# CAN_Sheet.net
KiCad netlist of a schematic drawn in Altium Designer
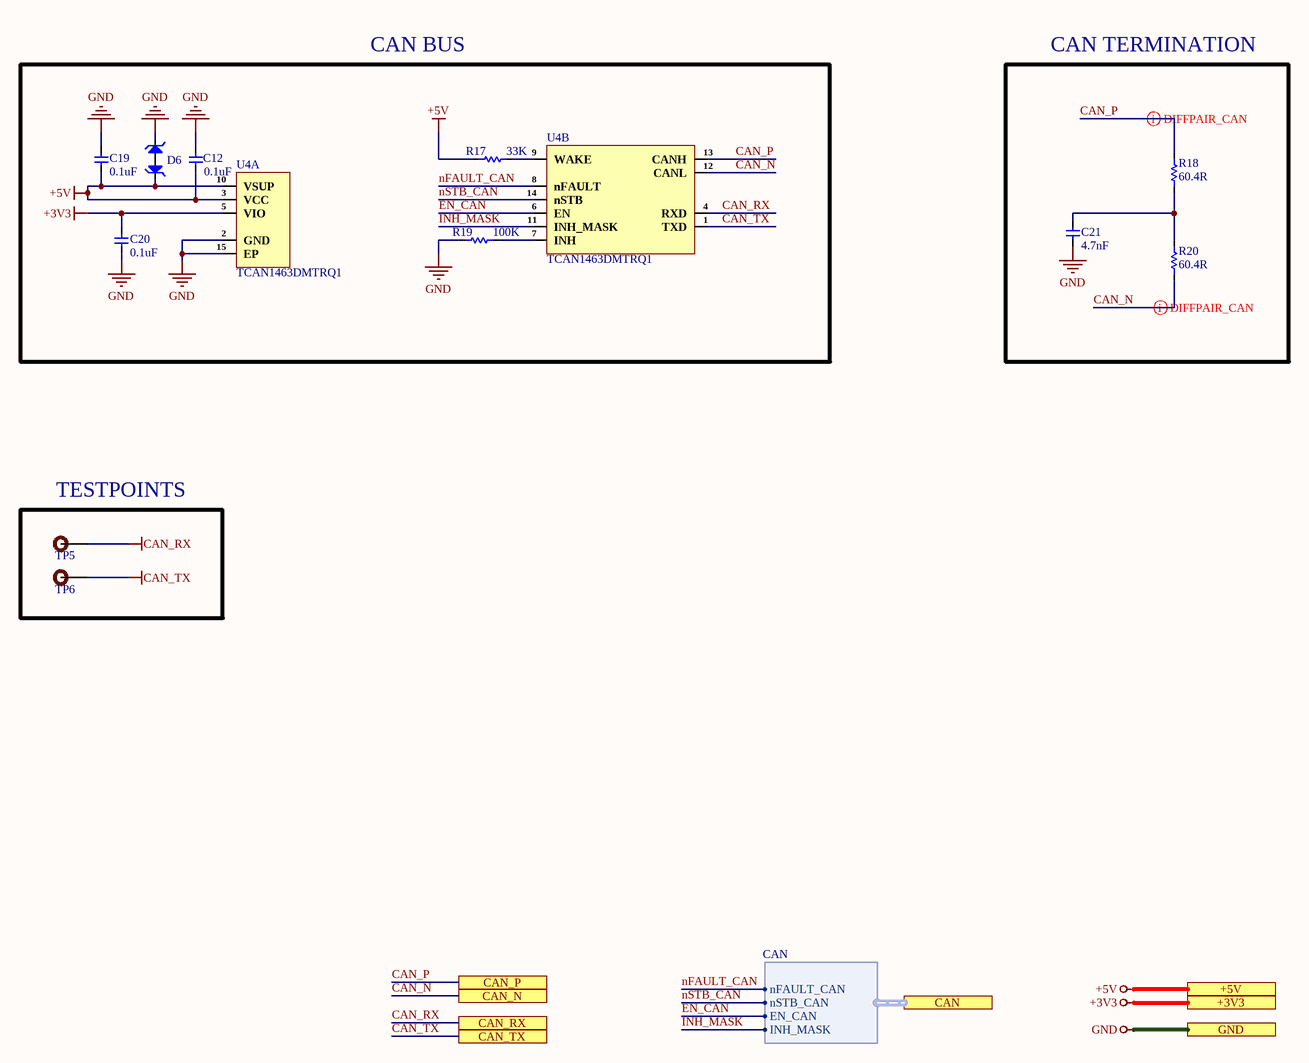
[diagram p0: CAN_Sheet.SchDoc]

(export (version "E")
  (design (tool "Eeschema 10.0.6"))
  (components
    (comp (ref "C12")
      (value "0.1uF")
      (footprint "Cap-0402")
      (description "CAP CER 0.1UF 16V X7R 0402")
      (fields
        (field (name "MANUFACTURER") "Yageo")
        (field (name "MANUFACTURER PART NUMBER") "CC0402JRX7R7BB104")
      )
      (libsource (lib "eSpark Libraries") (part "CC0402JRX7R7BB104"))
    )
    (comp (ref "C19")
      (value "0.1uF")
      (footprint "Cap-0402")
      (description "CAP CER 0.1UF 16V X7R 0402")
      (fields
        (field (name "MANUFACTURER") "Yageo")
        (field (name "MANUFACTURER PART NUMBER") "CC0402JRX7R7BB104")
      )
      (libsource (lib "eSpark Libraries") (part "CC0402JRX7R7BB104"))
    )
    (comp (ref "C20")
      (value "0.1uF")
      (footprint "Cap-0402")
      (description "CAP CER 0.1UF 16V X7R 0402")
      (fields
        (field (name "MANUFACTURER") "Yageo")
        (field (name "MANUFACTURER PART NUMBER") "CC0402JRX7R7BB104")
      )
      (libsource (lib "eSpark Libraries") (part "CC0402JRX7R7BB104"))
    )
    (comp (ref "C21")
      (value "4.7nF")
      (footprint "Cap-0402")
      (description "CAP CER 4700PF 50V X7R 0402")
      (fields
        (field (name "MANUFACTURER") "Yageo")
        (field (name "MANUFACTURER PART NUMBER") "CC0402KRX7R9BB472")
      )
      (libsource (lib "eSpark Libraries") (part "CC0402KRX7R9BB472"))
    )
    (comp (ref "D6")
      (value "PESD5V0H1BSFYL")
      (footprint "DSN0603-2")
      (description "TVS DIODE 5VWM 6.3VC DSN0603-2")
      (fields (field (name "MANUFACTURER") "Nexperia") (field (name "LCSC PART NUMBER") "C477989"))
      (libsource (lib "eSpark Libraries") (part "PESD5V0H1BSFYL"))
    )
    (comp (ref "R17")
      (value "33K")
      (footprint "Res-0402")
      (description "RES 33K OHM 1% 1/16W 0402")
      (fields
        (field (name "MANUFACTURER") "YAGEO")
        (field (name "MANUFACTURER PART NUMBER") "RC0402FR-0733KL")
      )
      (libsource (lib "eSpark Libraries") (part "RC0402FR-0733KL"))
    )
    (comp (ref "R18")
      (value "60.4R")
      (footprint "Res-0603")
      (description "100mW Thick Film Resistors ±100ppm/℃ ±1% 60.4Ω 0603 Chip Resistor - Surface Mount ROHS")
      (fields
        (field (name "MANUFACTURER PART NUMBER") "RTT0360R4FTP")
        (field (name "LCSC PART NUMBER") "C103744")
      )
      (libsource (lib "eSpark Libraries") (part "RTT0360R4FTP"))
    )
    (comp (ref "R19")
      (value "100K")
      (footprint "Res-0402")
      (description "RES 100K OHM 1% 1/16W 0402")
      (fields
        (field (name "MANUFACTURER") "Yageo")
        (field (name "MANUFACTURER PART NUMBER") "RC0402FR-07100KL")
      )
      (libsource (lib "eSpark Libraries") (part "RC0402FR-07100KL"))
    )
    (comp (ref "R20")
      (value "60.4R")
      (footprint "Res-0603")
      (description "100mW Thick Film Resistors ±100ppm/℃ ±1% 60.4Ω 0603 Chip Resistor - Surface Mount ROHS")
      (fields
        (field (name "MANUFACTURER PART NUMBER") "RTT0360R4FTP")
        (field (name "LCSC PART NUMBER") "C103744")
      )
      (libsource (lib "eSpark Libraries") (part "RTT0360R4FTP"))
    )
    (comp (ref "TP5")
      (value "TEST POINT")
      (footprint "Test-point")
      (description "Test Point ON")
      (libsource (lib "eSpark Libraries") (part "TEST POINT"))
    )
    (comp (ref "TP6")
      (value "TEST POINT")
      (footprint "Test-point")
      (description "Test Point ON")
      (libsource (lib "eSpark Libraries") (part "TEST POINT"))
    )
    (comp (ref "U4")
      (value "TCAN1463DMTRQ1")
      (footprint "VSON-14(3x4.5)")
      (description "IC TRANSCEIVER HALF 1/1 14VSON")
      (fields (field (name "MANUFACTURER") "Texas Instruments") (field (name "LCSC PART NUMBER") "C5215823"))
      (libsource (lib "eSpark Libraries") (part "TCAN1463DMTRQ1"))
    )
  )
  (nets
    (net (code "2") (name "+3V3") (class "Default")
      (node (ref "C20") (pin "2") (pinfunction "2_2") (pintype "passive"))
      (node (ref "U4") (pin "5") (pinfunction "VIO_5") (pintype "passive"))
    )
    (net (code "3") (name "+5V") (class "Default")
      (node (ref "C12") (pin "1") (pinfunction "1_1") (pintype "passive"))
      (node (ref "C19") (pin "1") (pinfunction "1_1") (pintype "passive"))
      (node (ref "D6") (pin "1") (pinfunction "1_1") (pintype "passive"))
      (node (ref "R17") (pin "1") (pinfunction "1_1") (pintype "passive"))
      (node (ref "U4") (pin "10") (pinfunction "VSUP_10") (pintype "passive"))
      (node (ref "U4") (pin "3") (pinfunction "VCC_3") (pintype "passive"))
    )
    (net (code "4") (name "/CAN_N") (class "Default")
      (node (ref "R20") (pin "2") (pinfunction "2_2") (pintype "passive"))
      (node (ref "U4") (pin "12") (pinfunction "CANL_12") (pintype "passive"))
    )
    (net (code "5") (name "/CAN_P") (class "Default")
      (node (ref "R18") (pin "1") (pinfunction "1_1") (pintype "passive"))
      (node (ref "U4") (pin "13") (pinfunction "CANH_13") (pintype "passive"))
    )
    (net (code "6") (name "/EN_CAN") (class "Default")
      (node (ref "U4") (pin "6") (pinfunction "EN_6") (pintype "passive"))
    )
    (net (code "7") (name "/INH_MASK") (class "Default")
      (node (ref "U4") (pin "11") (pinfunction "INH_MASK_11") (pintype "passive"))
    )
    (net (code "8") (name "/nFAULT_CAN") (class "Default")
      (node (ref "U4") (pin "8") (pinfunction "nFAULT_8") (pintype "passive"))
    )
    (net (code "9") (name "/nSTB_CAN") (class "Default")
      (node (ref "U4") (pin "14") (pinfunction "nSTB_14") (pintype "passive"))
    )
    (net (code "11") (name "CAN_RX") (class "Default")
      (node (ref "TP5") (pin "1") (pinfunction "1_1") (pintype "passive"))
      (node (ref "U4") (pin "4") (pinfunction "RXD_4") (pintype "passive"))
    )
    (net (code "12") (name "CAN_TX") (class "Default")
      (node (ref "TP6") (pin "1") (pinfunction "1_1") (pintype "passive"))
      (node (ref "U4") (pin "1") (pinfunction "TXD_1") (pintype "passive"))
    )
    (net (code "13") (name "GND") (class "Default")
      (node (ref "C12") (pin "2") (pinfunction "2_2") (pintype "passive"))
      (node (ref "C19") (pin "2") (pinfunction "2_2") (pintype "passive"))
      (node (ref "C20") (pin "1") (pinfunction "1_1") (pintype "passive"))
      (node (ref "C21") (pin "2") (pinfunction "2_2") (pintype "passive"))
      (node (ref "D6") (pin "2") (pinfunction "2_2") (pintype "passive"))
      (node (ref "R19") (pin "1") (pinfunction "1_1") (pintype "passive"))
      (node (ref "U4") (pin "15") (pinfunction "EP_15") (pintype "passive"))
      (node (ref "U4") (pin "2") (pinfunction "GND_2") (pintype "passive"))
    )
    (net (code "14") (name "Net-(C21-Pad1)") (class "Default")
      (node (ref "C21") (pin "1") (pinfunction "1_1") (pintype "passive"))
      (node (ref "R18") (pin "2") (pinfunction "2_2") (pintype "passive"))
      (node (ref "R20") (pin "1") (pinfunction "1_1") (pintype "passive"))
    )
    (net (code "15") (name "Net-(U4B-INH)") (class "Default")
      (node (ref "R19") (pin "2") (pinfunction "2_2") (pintype "passive"))
      (node (ref "U4") (pin "7") (pinfunction "INH_7") (pintype "passive"))
    )
    (net (code "16") (name "Net-(U4B-WAKE)") (class "Default")
      (node (ref "R17") (pin "2") (pinfunction "2_2") (pintype "passive"))
      (node (ref "U4") (pin "9") (pinfunction "WAKE_9") (pintype "passive"))
    )
  )
)
